# NeoDigito_Medio_v2.net
KiCad netlist of a schematic drawn in EAGLE
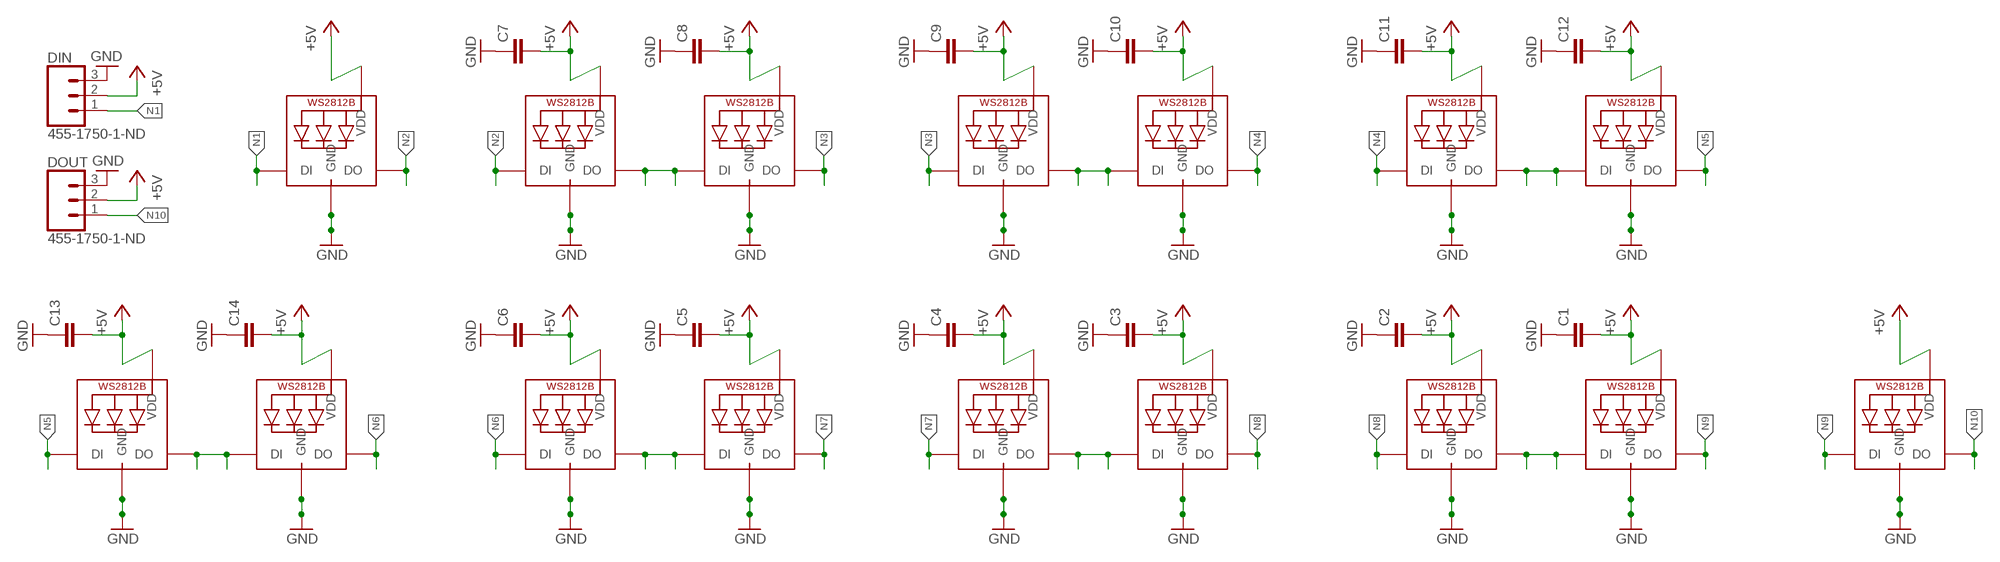
[diagram p0: schematic, sheet 1]

(export (version "E")
  (design (tool "Eeschema 10.0.6"))
  (components
    (comp (ref "C1")
      (value "C-EUC0805")
      (footprint "eagle-import:C0805")
      (libsource (lib "eagle-import") (part "C-EUC0805"))
    )
    (comp (ref "C2")
      (value "C-EUC0805")
      (footprint "eagle-import:C0805")
      (libsource (lib "eagle-import") (part "C-EUC0805"))
    )
    (comp (ref "C3")
      (value "C-EUC0805")
      (footprint "eagle-import:C0805")
      (libsource (lib "eagle-import") (part "C-EUC0805"))
    )
    (comp (ref "C4")
      (value "C-EUC0805")
      (footprint "eagle-import:C0805")
      (libsource (lib "eagle-import") (part "C-EUC0805"))
    )
    (comp (ref "C5")
      (value "C-EUC0805")
      (footprint "eagle-import:C0805")
      (libsource (lib "eagle-import") (part "C-EUC0805"))
    )
    (comp (ref "C6")
      (value "C-EUC0805")
      (footprint "eagle-import:C0805")
      (libsource (lib "eagle-import") (part "C-EUC0805"))
    )
    (comp (ref "C7")
      (value "C-EUC0805")
      (footprint "eagle-import:C0805")
      (libsource (lib "eagle-import") (part "C-EUC0805"))
    )
    (comp (ref "C8")
      (value "C-EUC0805")
      (footprint "eagle-import:C0805")
      (libsource (lib "eagle-import") (part "C-EUC0805"))
    )
    (comp (ref "C9")
      (value "C-EUC0805")
      (footprint "eagle-import:C0805")
      (libsource (lib "eagle-import") (part "C-EUC0805"))
    )
    (comp (ref "C10")
      (value "C-EUC0805")
      (footprint "eagle-import:C0805")
      (libsource (lib "eagle-import") (part "C-EUC0805"))
    )
    (comp (ref "C11")
      (value "C-EUC0805")
      (footprint "eagle-import:C0805")
      (libsource (lib "eagle-import") (part "C-EUC0805"))
    )
    (comp (ref "C12")
      (value "C-EUC0805")
      (footprint "eagle-import:C0805")
      (libsource (lib "eagle-import") (part "C-EUC0805"))
    )
    (comp (ref "C13")
      (value "C-EUC0805")
      (footprint "eagle-import:C0805")
      (libsource (lib "eagle-import") (part "C-EUC0805"))
    )
    (comp (ref "C14")
      (value "C-EUC0805")
      (footprint "eagle-import:C0805")
      (libsource (lib "eagle-import") (part "C-EUC0805"))
    )
    (comp (ref "DIN")
      (value "455-1750-1-ND")
      (footprint "eagle-import:1X03")
      (libsource (lib "eagle-import") (part "CONN_03"))
    )
    (comp (ref "DOUT")
      (value "455-1750-1-ND")
      (footprint "eagle-import:1X03_NO_SILK")
      (libsource (lib "eagle-import") (part "CONN_031X03_NO_SILK"))
    )
    (comp (ref "PA.")
      (value "WS2812B3535")
      (footprint "eagle-import:LED3535")
      (libsource (lib "eagle-import") (part "WS2812B3535"))
    )
    (comp (ref "PB.")
      (value "WS2812B3535")
      (footprint "eagle-import:LED3535")
      (libsource (lib "eagle-import") (part "WS2812B3535"))
    )
    (comp (ref "SA1.")
      (value "WS2812B3535")
      (footprint "eagle-import:LED3535")
      (libsource (lib "eagle-import") (part "WS2812B3535"))
    )
    (comp (ref "SA2.")
      (value "WS2812B3535")
      (footprint "eagle-import:LED3535")
      (libsource (lib "eagle-import") (part "WS2812B3535"))
    )
    (comp (ref "SB1.")
      (value "WS2812B3535")
      (footprint "eagle-import:LED3535")
      (libsource (lib "eagle-import") (part "WS2812B3535"))
    )
    (comp (ref "SB2.")
      (value "WS2812B3535")
      (footprint "eagle-import:LED3535")
      (libsource (lib "eagle-import") (part "WS2812B3535"))
    )
    (comp (ref "SC1.")
      (value "WS2812B3535")
      (footprint "eagle-import:LED3535")
      (libsource (lib "eagle-import") (part "WS2812B3535"))
    )
    (comp (ref "SC2.")
      (value "WS2812B3535")
      (footprint "eagle-import:LED3535")
      (libsource (lib "eagle-import") (part "WS2812B3535"))
    )
    (comp (ref "SD1.")
      (value "WS2812B3535")
      (footprint "eagle-import:LED3535")
      (libsource (lib "eagle-import") (part "WS2812B3535"))
    )
    (comp (ref "SD2.")
      (value "WS2812B3535")
      (footprint "eagle-import:LED3535")
      (libsource (lib "eagle-import") (part "WS2812B3535"))
    )
    (comp (ref "SE1.")
      (value "WS2812B3535")
      (footprint "eagle-import:LED3535")
      (libsource (lib "eagle-import") (part "WS2812B3535"))
    )
    (comp (ref "SE2.")
      (value "WS2812B3535")
      (footprint "eagle-import:LED3535")
      (libsource (lib "eagle-import") (part "WS2812B3535"))
    )
    (comp (ref "SF1.")
      (value "WS2812B3535")
      (footprint "eagle-import:LED3535")
      (libsource (lib "eagle-import") (part "WS2812B3535"))
    )
    (comp (ref "SF2.")
      (value "WS2812B3535")
      (footprint "eagle-import:LED3535")
      (libsource (lib "eagle-import") (part "WS2812B3535"))
    )
    (comp (ref "SG1.")
      (value "WS2812B3535")
      (footprint "eagle-import:LED3535")
      (libsource (lib "eagle-import") (part "WS2812B3535"))
    )
    (comp (ref "SG2.")
      (value "WS2812B3535")
      (footprint "eagle-import:LED3535")
      (libsource (lib "eagle-import") (part "WS2812B3535"))
    )
  )
  (nets
    (net (code "1") (name "+5V") (class "Default")
      (node (ref "C1") (pin "2") (pinfunction "2_2") (pintype "passive"))
      (node (ref "C10") (pin "2") (pinfunction "2_2") (pintype "passive"))
      (node (ref "C11") (pin "2") (pinfunction "2_2") (pintype "passive"))
      (node (ref "C12") (pin "2") (pinfunction "2_2") (pintype "passive"))
      (node (ref "C13") (pin "2") (pinfunction "2_2") (pintype "passive"))
      (node (ref "C14") (pin "2") (pinfunction "2_2") (pintype "passive"))
      (node (ref "C2") (pin "2") (pinfunction "2_2") (pintype "passive"))
      (node (ref "C3") (pin "2") (pinfunction "2_2") (pintype "passive"))
      (node (ref "C4") (pin "2") (pinfunction "2_2") (pintype "passive"))
      (node (ref "C5") (pin "2") (pinfunction "2_2") (pintype "passive"))
      (node (ref "C6") (pin "2") (pinfunction "2_2") (pintype "passive"))
      (node (ref "C7") (pin "2") (pinfunction "2_2") (pintype "passive"))
      (node (ref "C8") (pin "2") (pinfunction "2_2") (pintype "passive"))
      (node (ref "C9") (pin "2") (pinfunction "2_2") (pintype "passive"))
      (node (ref "DIN") (pin "2") (pinfunction "2_2") (pintype "passive"))
      (node (ref "DOUT") (pin "2") (pinfunction "2_2") (pintype "passive"))
      (node (ref "PA.") (pin "2") (pinfunction "VDD_2") (pintype "power_in"))
      (node (ref "PB.") (pin "2") (pinfunction "VDD_2") (pintype "power_in"))
      (node (ref "SA1.") (pin "2") (pinfunction "VDD_2") (pintype "power_in"))
      (node (ref "SA2.") (pin "2") (pinfunction "VDD_2") (pintype "power_in"))
      (node (ref "SB1.") (pin "2") (pinfunction "VDD_2") (pintype "power_in"))
      (node (ref "SB2.") (pin "2") (pinfunction "VDD_2") (pintype "power_in"))
      (node (ref "SC1.") (pin "2") (pinfunction "VDD_2") (pintype "power_in"))
      (node (ref "SC2.") (pin "2") (pinfunction "VDD_2") (pintype "power_in"))
      (node (ref "SD1.") (pin "2") (pinfunction "VDD_2") (pintype "power_in"))
      (node (ref "SD2.") (pin "2") (pinfunction "VDD_2") (pintype "power_in"))
      (node (ref "SE1.") (pin "2") (pinfunction "VDD_2") (pintype "power_in"))
      (node (ref "SE2.") (pin "2") (pinfunction "VDD_2") (pintype "power_in"))
      (node (ref "SF1.") (pin "2") (pinfunction "VDD_2") (pintype "power_in"))
      (node (ref "SF2.") (pin "2") (pinfunction "VDD_2") (pintype "power_in"))
      (node (ref "SG1.") (pin "2") (pinfunction "VDD_2") (pintype "power_in"))
      (node (ref "SG2.") (pin "2") (pinfunction "VDD_2") (pintype "power_in"))
    )
    (net (code "2") (name "GND") (class "Default")
      (node (ref "C1") (pin "1") (pinfunction "1_1") (pintype "passive"))
      (node (ref "C10") (pin "1") (pinfunction "1_1") (pintype "passive"))
      (node (ref "C11") (pin "1") (pinfunction "1_1") (pintype "passive"))
      (node (ref "C12") (pin "1") (pinfunction "1_1") (pintype "passive"))
      (node (ref "C13") (pin "1") (pinfunction "1_1") (pintype "passive"))
      (node (ref "C14") (pin "1") (pinfunction "1_1") (pintype "passive"))
      (node (ref "C2") (pin "1") (pinfunction "1_1") (pintype "passive"))
      (node (ref "C3") (pin "1") (pinfunction "1_1") (pintype "passive"))
      (node (ref "C4") (pin "1") (pinfunction "1_1") (pintype "passive"))
      (node (ref "C5") (pin "1") (pinfunction "1_1") (pintype "passive"))
      (node (ref "C6") (pin "1") (pinfunction "1_1") (pintype "passive"))
      (node (ref "C7") (pin "1") (pinfunction "1_1") (pintype "passive"))
      (node (ref "C8") (pin "1") (pinfunction "1_1") (pintype "passive"))
      (node (ref "C9") (pin "1") (pinfunction "1_1") (pintype "passive"))
      (node (ref "DIN") (pin "3") (pinfunction "3_3") (pintype "passive"))
      (node (ref "DOUT") (pin "3") (pinfunction "3_3") (pintype "passive"))
      (node (ref "PA.") (pin "4") (pinfunction "GND_4") (pintype "power_in"))
      (node (ref "PB.") (pin "4") (pinfunction "GND_4") (pintype "power_in"))
      (node (ref "SA1.") (pin "4") (pinfunction "GND_4") (pintype "power_in"))
      (node (ref "SA2.") (pin "4") (pinfunction "GND_4") (pintype "power_in"))
      (node (ref "SB1.") (pin "4") (pinfunction "GND_4") (pintype "power_in"))
      (node (ref "SB2.") (pin "4") (pinfunction "GND_4") (pintype "power_in"))
      (node (ref "SC1.") (pin "4") (pinfunction "GND_4") (pintype "power_in"))
      (node (ref "SC2.") (pin "4") (pinfunction "GND_4") (pintype "power_in"))
      (node (ref "SD1.") (pin "4") (pinfunction "GND_4") (pintype "power_in"))
      (node (ref "SD2.") (pin "4") (pinfunction "GND_4") (pintype "power_in"))
      (node (ref "SE1.") (pin "4") (pinfunction "GND_4") (pintype "power_in"))
      (node (ref "SE2.") (pin "4") (pinfunction "GND_4") (pintype "power_in"))
      (node (ref "SF1.") (pin "4") (pinfunction "GND_4") (pintype "power_in"))
      (node (ref "SF2.") (pin "4") (pinfunction "GND_4") (pintype "power_in"))
      (node (ref "SG1.") (pin "4") (pinfunction "GND_4") (pintype "power_in"))
      (node (ref "SG2.") (pin "4") (pinfunction "GND_4") (pintype "power_in"))
    )
    (net (code "3") (name "N1") (class "Default")
      (node (ref "DIN") (pin "1") (pinfunction "1_1") (pintype "passive"))
      (node (ref "PB.") (pin "1") (pinfunction "DI_1") (pintype "input"))
    )
    (net (code "4") (name "N2") (class "Default")
      (node (ref "PB.") (pin "3") (pinfunction "DO_3") (pintype "output"))
      (node (ref "SC1.") (pin "1") (pinfunction "DI_1") (pintype "input"))
    )
    (net (code "5") (name "N3") (class "Default")
      (node (ref "SC2.") (pin "3") (pinfunction "DO_3") (pintype "output"))
      (node (ref "SD1.") (pin "1") (pinfunction "DI_1") (pintype "input"))
    )
    (net (code "6") (name "N4") (class "Default")
      (node (ref "SD2.") (pin "3") (pinfunction "DO_3") (pintype "output"))
      (node (ref "SE1.") (pin "1") (pinfunction "DI_1") (pintype "input"))
    )
    (net (code "7") (name "N5") (class "Default")
      (node (ref "SE2.") (pin "3") (pinfunction "DO_3") (pintype "output"))
      (node (ref "SG1.") (pin "1") (pinfunction "DI_1") (pintype "input"))
    )
    (net (code "8") (name "N6") (class "Default")
      (node (ref "SB1.") (pin "1") (pinfunction "DI_1") (pintype "input"))
      (node (ref "SG2.") (pin "3") (pinfunction "DO_3") (pintype "output"))
    )
    (net (code "9") (name "N7") (class "Default")
      (node (ref "SA1.") (pin "1") (pinfunction "DI_1") (pintype "input"))
      (node (ref "SB2.") (pin "3") (pinfunction "DO_3") (pintype "output"))
    )
    (net (code "10") (name "N8") (class "Default")
      (node (ref "SA2.") (pin "3") (pinfunction "DO_3") (pintype "output"))
      (node (ref "SF1.") (pin "1") (pinfunction "DI_1") (pintype "input"))
    )
    (net (code "11") (name "N9") (class "Default")
      (node (ref "PA.") (pin "1") (pinfunction "DI_1") (pintype "input"))
      (node (ref "SF2.") (pin "3") (pinfunction "DO_3") (pintype "output"))
    )
    (net (code "12") (name "N10") (class "Default")
      (node (ref "DOUT") (pin "1") (pinfunction "1_1") (pintype "passive"))
      (node (ref "PA.") (pin "3") (pinfunction "DO_3") (pintype "output"))
    )
    (net (code "13") (name "Net-(SA1.-DO)") (class "Default")
      (node (ref "SA1.") (pin "3") (pinfunction "DO_3") (pintype "output"))
      (node (ref "SA2.") (pin "1") (pinfunction "DI_1") (pintype "input"))
    )
    (net (code "14") (name "Net-(SB1.-DO)") (class "Default")
      (node (ref "SB1.") (pin "3") (pinfunction "DO_3") (pintype "output"))
      (node (ref "SB2.") (pin "1") (pinfunction "DI_1") (pintype "input"))
    )
    (net (code "15") (name "Net-(SC1.-DO)") (class "Default")
      (node (ref "SC1.") (pin "3") (pinfunction "DO_3") (pintype "output"))
      (node (ref "SC2.") (pin "1") (pinfunction "DI_1") (pintype "input"))
    )
    (net (code "16") (name "Net-(SD1.-DO)") (class "Default")
      (node (ref "SD1.") (pin "3") (pinfunction "DO_3") (pintype "output"))
      (node (ref "SD2.") (pin "1") (pinfunction "DI_1") (pintype "input"))
    )
    (net (code "17") (name "Net-(SE1.-DO)") (class "Default")
      (node (ref "SE1.") (pin "3") (pinfunction "DO_3") (pintype "output"))
      (node (ref "SE2.") (pin "1") (pinfunction "DI_1") (pintype "input"))
    )
    (net (code "18") (name "Net-(SF1.-DO)") (class "Default")
      (node (ref "SF1.") (pin "3") (pinfunction "DO_3") (pintype "output"))
      (node (ref "SF2.") (pin "1") (pinfunction "DI_1") (pintype "input"))
    )
    (net (code "19") (name "Net-(SG1.-DO)") (class "Default")
      (node (ref "SG1.") (pin "3") (pinfunction "DO_3") (pintype "output"))
      (node (ref "SG2.") (pin "1") (pinfunction "DI_1") (pintype "input"))
    )
  )
)
